# livestream.net
KiCad netlist of a schematic drawn in Altium Designer
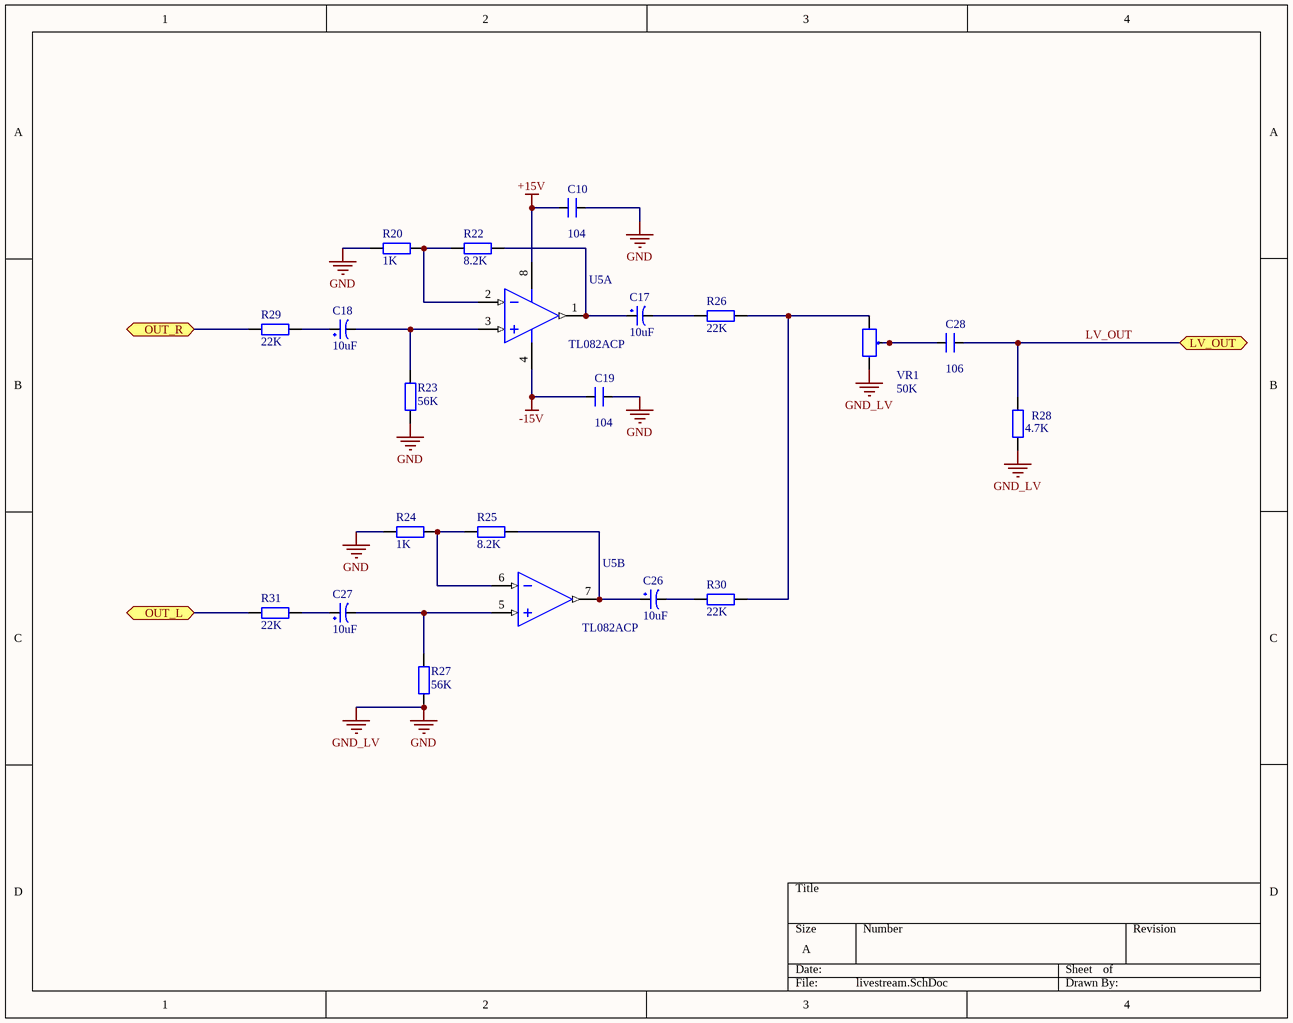
[diagram p0: livestream.SchDoc]

(export (version "E")
  (design (tool "Eeschema 10.0.6"))
  (components
    (comp (ref "C10")
      (value "104")
      (footprint "0805_HV")
      (libsource (lib "MH_DA_THU_VIEN_16122016") (part "TU_MICA_ 104 100V(2A104J)_MH"))
    )
    (comp (ref "C17")
      (value "10uF")
      (footprint "0805_HV")
      (description "TU_HOA_4.7uF_100V_MH")
      (libsource (lib "MH_DA_THU_VIEN_16122016") (part "TU_HOA_4.7uF_100V_MH"))
    )
    (comp (ref "C18")
      (value "10uF")
      (footprint "0805_HV")
      (libsource (lib "MH_DA_THU_VIEN_16122016") (part "TU_HOA_10uF_16V_MH"))
    )
    (comp (ref "C19")
      (value "104")
      (footprint "0805_HV")
      (libsource (lib "MH_DA_THU_VIEN_16122016") (part "TU_MICA_ 104 100V(2A104J)_MH"))
    )
    (comp (ref "C26")
      (value "10uF")
      (footprint "0805_HV")
      (description "TU_HOA_4.7uF_100V_MH")
      (libsource (lib "MH_DA_THU_VIEN_16122016") (part "TU_HOA_4.7uF_100V_MH"))
    )
    (comp (ref "C27")
      (value "10uF")
      (footprint "0805_HV")
      (libsource (lib "MH_DA_THU_VIEN_16122016") (part "TU_HOA_10uF_16V_MH"))
    )
    (comp (ref "C28")
      (value "106")
      (footprint "0805_HV")
      (libsource (lib "MH_DA_THU_VIEN_16122016") (part "TU_MICA_ 104 100V(2A104J)_MH"))
    )
    (comp (ref "R20")
      (value "1K")
      (footprint "0805_HV")
      (libsource (lib "MH_DA_THU_VIEN_16122016") (part "TRO_VACH_1/4W_MH"))
    )
    (comp (ref "R22")
      (value "8.2K")
      (footprint "0805_HV")
      (libsource (lib "MH_DA_THU_VIEN_16122016") (part "TRO_VACH_1/4W_MH"))
    )
    (comp (ref "R23")
      (value "56K")
      (footprint "0805_HV")
      (libsource (lib "MH_DA_THU_VIEN_16122016") (part "TRO_VACH_1/4W_MH"))
    )
    (comp (ref "R24")
      (value "1K")
      (footprint "0805_HV")
      (libsource (lib "MH_DA_THU_VIEN_16122016") (part "TRO_VACH_1/4W_MH"))
    )
    (comp (ref "R25")
      (value "8.2K")
      (footprint "0805_HV")
      (libsource (lib "MH_DA_THU_VIEN_16122016") (part "TRO_VACH_1/4W_MH"))
    )
    (comp (ref "R26")
      (value "22K")
      (footprint "0805_HV")
      (libsource (lib "MH_DA_THU_VIEN_16122016") (part "TRO_VACH_1/4W_MH"))
    )
    (comp (ref "R27")
      (value "56K")
      (footprint "0805_HV")
      (libsource (lib "MH_DA_THU_VIEN_16122016") (part "TRO_VACH_1/4W_MH"))
    )
    (comp (ref "R28")
      (value "4.7K")
      (footprint "0805_HV")
      (libsource (lib "MH_DA_THU_VIEN_16122016") (part "TRO_VACH_1/4W_MH"))
    )
    (comp (ref "R29")
      (value "22K")
      (footprint "0805_HV")
      (libsource (lib "MH_DA_THU_VIEN_16122016") (part "TRO_VACH_1/4W_MH"))
    )
    (comp (ref "R30")
      (value "22K")
      (footprint "0805_HV")
      (libsource (lib "MH_DA_THU_VIEN_16122016") (part "TRO_VACH_1/4W_MH"))
    )
    (comp (ref "R31")
      (value "22K")
      (footprint "0805_HV")
      (libsource (lib "MH_DA_THU_VIEN_16122016") (part "TRO_VACH_1/4W_MH"))
    )
    (comp (ref "U5")
      (value "TL082ACP")
      (footprint "SOP 8")
      (description "JFET-Input Operational Amplifier")
      (fields (field (name "PUBLISHER") "Altium Limited"))
      (libsource (lib "Schlib1") (part "TL082ACP"))
    )
    (comp (ref "VR1")
      (value "50K")
      (footprint "VR-3V")
      (description "VR-vuong")
      (libsource (lib "MH_DA_THU_VIEN_16122016") (part "BIEN_TRO_VR 204-200K 3296W_MH"))
    )
  )
  (nets
    (net (code "1") (name "+15V") (class "Default")
      (node (ref "C10") (pin "1") (pinfunction "1_1") (pintype "passive"))
      (node (ref "U5") (pin "8") (pinfunction "V+_8") (pintype "power_in"))
    )
    (net (code "2") (name "-15V") (class "Default")
      (node (ref "C19") (pin "1") (pinfunction "1_1") (pintype "passive"))
      (node (ref "U5") (pin "4") (pinfunction "V-_4") (pintype "power_in"))
    )
    (net (code "3") (name "/LV_OUT") (class "Default")
      (node (ref "C28") (pin "2") (pinfunction "2_2") (pintype "passive"))
      (node (ref "R28") (pin "1") (pinfunction "1_1") (pintype "passive"))
    )
    (net (code "4") (name "/OUT_L") (class "Default")
      (node (ref "R31") (pin "1") (pinfunction "1_1") (pintype "passive"))
    )
    (net (code "5") (name "/OUT_R") (class "Default")
      (node (ref "R29") (pin "1") (pinfunction "1_1") (pintype "passive"))
    )
    (net (code "6") (name "GND") (class "Default")
      (node (ref "C10") (pin "2") (pinfunction "2_2") (pintype "passive"))
      (node (ref "C19") (pin "2") (pinfunction "2_2") (pintype "passive"))
      (node (ref "R20") (pin "1") (pinfunction "1_1") (pintype "passive"))
      (node (ref "R23") (pin "1") (pinfunction "1_1") (pintype "passive"))
      (node (ref "R24") (pin "1") (pinfunction "1_1") (pintype "passive"))
      (node (ref "R27") (pin "1") (pinfunction "1_1") (pintype "passive"))
      (node (ref "R28") (pin "2") (pinfunction "2_2") (pintype "passive"))
      (node (ref "VR1") (pin "3") (pinfunction "3_3") (pintype "passive"))
    )
    (net (code "7") (name "Net-(C17-Pad2)") (class "Default")
      (node (ref "C17") (pin "2") (pinfunction "2_2") (pintype "passive"))
      (node (ref "R26") (pin "1") (pinfunction "1_1") (pintype "passive"))
    )
    (net (code "8") (name "Net-(C18-Pad1)") (class "Default")
      (node (ref "C18") (pin "1") (pinfunction "1_1") (pintype "passive"))
      (node (ref "R29") (pin "2") (pinfunction "2_2") (pintype "passive"))
    )
    (net (code "9") (name "Net-(C26-Pad2)") (class "Default")
      (node (ref "C26") (pin "2") (pinfunction "2_2") (pintype "passive"))
      (node (ref "R30") (pin "1") (pinfunction "1_1") (pintype "passive"))
    )
    (net (code "10") (name "Net-(C27-Pad1)") (class "Default")
      (node (ref "C27") (pin "1") (pinfunction "1_1") (pintype "passive"))
      (node (ref "R31") (pin "2") (pinfunction "2_2") (pintype "passive"))
    )
    (net (code "11") (name "Net-(C28-Pad1)") (class "Default")
      (node (ref "C28") (pin "1") (pinfunction "1_1") (pintype "passive"))
      (node (ref "VR1") (pin "2") (pinfunction "2_2") (pintype "passive"))
    )
    (net (code "12") (name "Net-(R26-Pad2)") (class "Default")
      (node (ref "R26") (pin "2") (pinfunction "2_2") (pintype "passive"))
      (node (ref "R30") (pin "2") (pinfunction "2_2") (pintype "passive"))
      (node (ref "VR1") (pin "1") (pinfunction "1_1") (pintype "passive"))
    )
    (net (code "13") (name "Net-(U5A-IN+)") (class "Default")
      (node (ref "C18") (pin "2") (pinfunction "2_2") (pintype "passive"))
      (node (ref "R23") (pin "2") (pinfunction "2_2") (pintype "passive"))
      (node (ref "U5") (pin "3") (pinfunction "IN+_3") (pintype "input"))
    )
    (net (code "14") (name "Net-(U5A-IN-)") (class "Default")
      (node (ref "R20") (pin "2") (pinfunction "2_2") (pintype "passive"))
      (node (ref "R22") (pin "2") (pinfunction "2_2") (pintype "passive"))
      (node (ref "U5") (pin "2") (pinfunction "IN-_2") (pintype "input"))
    )
    (net (code "15") (name "Net-(U5A-OUT)") (class "Default")
      (node (ref "C17") (pin "1") (pinfunction "1_1") (pintype "passive"))
      (node (ref "R22") (pin "1") (pinfunction "1_1") (pintype "passive"))
      (node (ref "U5") (pin "1") (pinfunction "OUT_1") (pintype "output"))
    )
    (net (code "16") (name "Net-(U5B-IN+)") (class "Default")
      (node (ref "C27") (pin "2") (pinfunction "2_2") (pintype "passive"))
      (node (ref "R27") (pin "2") (pinfunction "2_2") (pintype "passive"))
      (node (ref "U5") (pin "5") (pinfunction "IN+_5") (pintype "input"))
    )
    (net (code "17") (name "Net-(U5B-IN-)") (class "Default")
      (node (ref "R24") (pin "2") (pinfunction "2_2") (pintype "passive"))
      (node (ref "R25") (pin "2") (pinfunction "2_2") (pintype "passive"))
      (node (ref "U5") (pin "6") (pinfunction "IN-_6") (pintype "input"))
    )
    (net (code "18") (name "Net-(U5B-OUT)") (class "Default")
      (node (ref "C26") (pin "1") (pinfunction "1_1") (pintype "passive"))
      (node (ref "R25") (pin "1") (pinfunction "1_1") (pintype "passive"))
      (node (ref "U5") (pin "7") (pinfunction "OUT_7") (pintype "output"))
    )
  )
)
